# design.net
KiCad netlist of a schematic drawn in Altium Designer
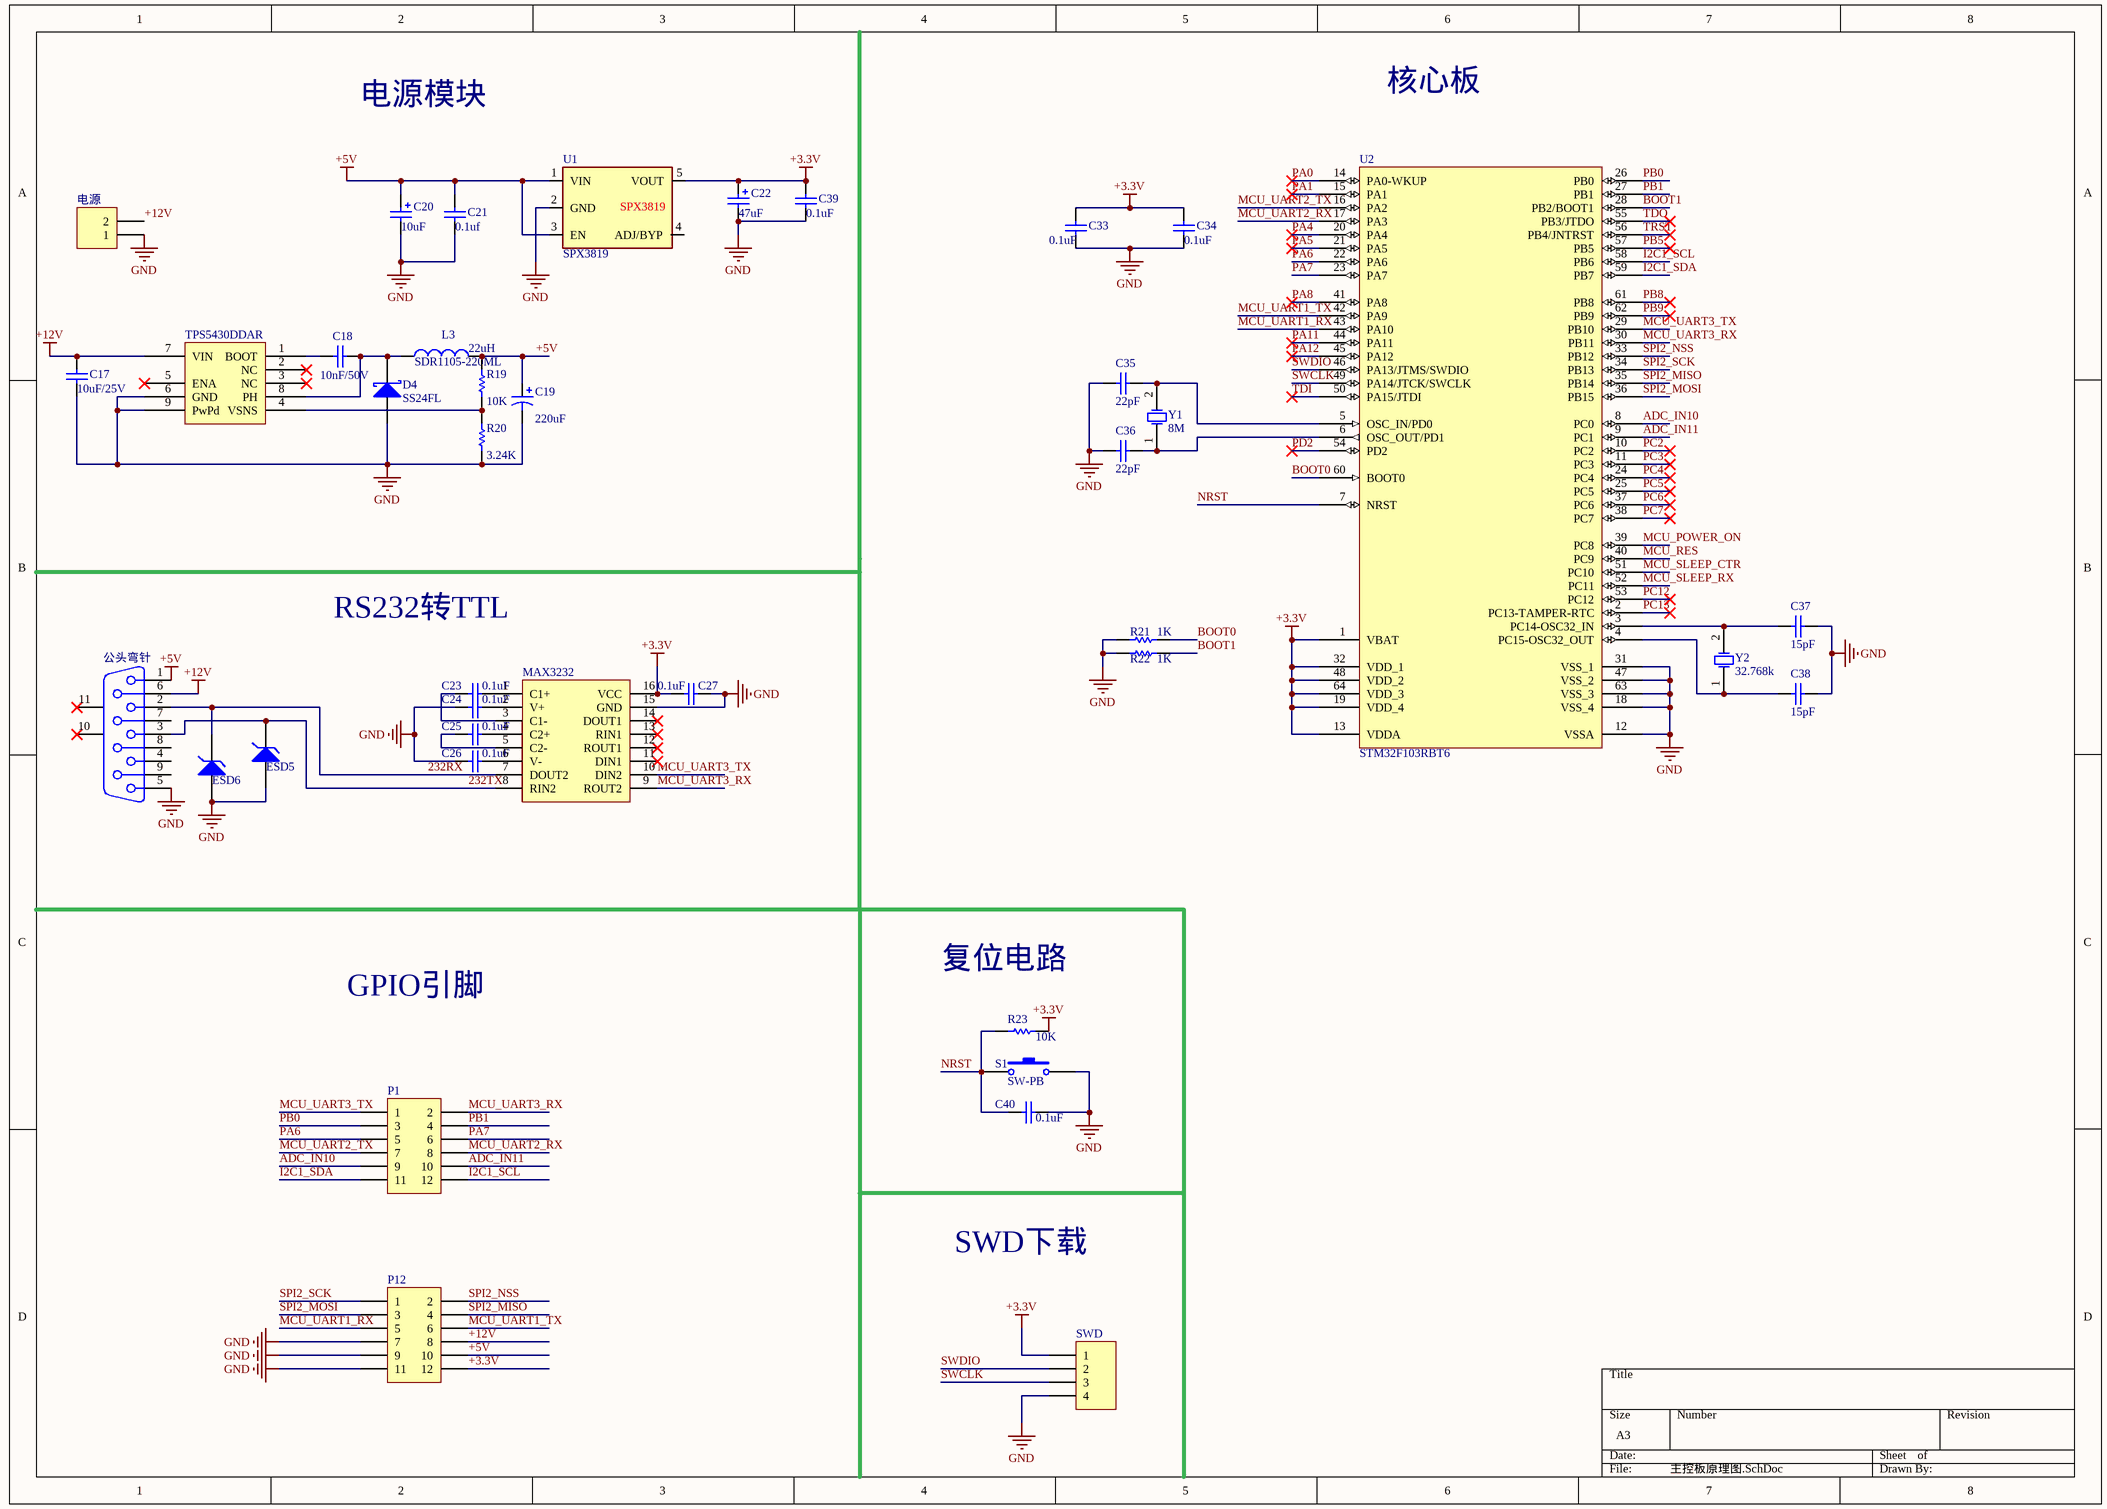
[diagram p0: 主控板原理图.SchDoc]

(export (version "E")
  (design (tool "Eeschema 10.0.6"))
  (components
    (comp (ref "C17")
      (value "10uF/25V")
      (footprint "1206")
      (description "Capacitor")
      (fields (field (name "Comment") "GRM31CR61E106KA12L") (field (name "PUBLISHER") "Altium Limited"))
      (libsource (lib "Miscellaneous Devices") (part "Cap"))
    )
    (comp (ref "C18")
      (value "10nF/50V")
      (footprint "0805")
      (description "Capacitor")
      (fields (field (name "Comment") "C0805C103K5RACTU") (field (name "PUBLISHER") "Altium Limited"))
      (libsource (lib "Miscellaneous Devices") (part "Cap"))
    )
    (comp (ref "C19")
      (value "220uF")
      (footprint "钽电容(B)")
      (description "Polarized Capacitor (Radial)")
      (fields (field (name "Comment") "6TPE220MAZB") (field (name "PUBLISHER") "Altium Limited"))
      (libsource (lib "Miscellaneous Devices") (part "Cap Pol1"))
    )
    (comp (ref "C20")
      (value "10uF")
      (footprint "1206")
      (fields (field (name "Comment") "C1206-10uF"))
      (libsource (lib "四轴旋翼") (part "C100uF"))
    )
    (comp (ref "C21")
      (value "0.1uf")
      (footprint "0805")
      (fields (field (name "Comment") "104"))
      (libsource (lib "四轴旋翼") (part "C0.1uF"))
    )
    (comp (ref "C22")
      (value "47uF")
      (footprint "1206")
      (fields (field (name "Comment") "C1206-47uF"))
      (libsource (lib "四轴旋翼") (part "C100uF"))
    )
    (comp (ref "C23")
      (value "0.1uF")
      (footprint "0805")
      (description "Capacitor")
      (fields (field (name "Comment") "104") (field (name "PUBLISHER") "Altium Limited"))
      (libsource (lib "Miscellaneous Devices") (part "Cap"))
    )
    (comp (ref "C24")
      (value "0.1uF")
      (footprint "0805")
      (description "Capacitor")
      (fields (field (name "Comment") "104") (field (name "PUBLISHER") "Altium Limited"))
      (libsource (lib "Miscellaneous Devices") (part "Cap"))
    )
    (comp (ref "C25")
      (value "0.1uF")
      (footprint "0805")
      (description "Capacitor")
      (fields (field (name "Comment") "104") (field (name "PUBLISHER") "Altium Limited"))
      (libsource (lib "Miscellaneous Devices") (part "Cap"))
    )
    (comp (ref "C26")
      (value "0.1uF")
      (footprint "0805")
      (description "Capacitor")
      (fields (field (name "Comment") "104") (field (name "PUBLISHER") "Altium Limited"))
      (libsource (lib "Miscellaneous Devices") (part "Cap"))
    )
    (comp (ref "C27")
      (value "0.1uF")
      (footprint "0805")
      (description "Capacitor")
      (fields (field (name "Comment") "104") (field (name "PUBLISHER") "Altium Limited"))
      (libsource (lib "Miscellaneous Devices") (part "Cap"))
    )
    (comp (ref "C33")
      (value "0.1uF")
      (footprint "0805")
      (description "Capacitor")
      (fields (field (name "Comment") "104") (field (name "PUBLISHER") "Altium Limited"))
      (libsource (lib "Miscellaneous Devices") (part "Cap"))
    )
    (comp (ref "C34")
      (value "0.1uF")
      (footprint "0805")
      (description "Capacitor")
      (fields (field (name "Comment") "104") (field (name "PUBLISHER") "Altium Limited"))
      (libsource (lib "Miscellaneous Devices") (part "Cap"))
    )
    (comp (ref "C35")
      (value "22pF")
      (footprint "0805")
      (description "Capacitor")
      (fields (field (name "Comment") "22") (field (name "PUBLISHER") "Altium Limited"))
      (libsource (lib "Miscellaneous Devices") (part "Cap"))
    )
    (comp (ref "C36")
      (value "22pF")
      (footprint "0805")
      (description "Capacitor")
      (fields (field (name "Comment") "22") (field (name "PUBLISHER") "Altium Limited"))
      (libsource (lib "Miscellaneous Devices") (part "Cap"))
    )
    (comp (ref "C37")
      (value "15pF")
      (footprint "0805")
      (description "Capacitor")
      (fields (field (name "Comment") "15") (field (name "PUBLISHER") "Altium Limited"))
      (libsource (lib "Miscellaneous Devices") (part "Cap"))
    )
    (comp (ref "C38")
      (value "15pF")
      (footprint "0805")
      (description "Capacitor")
      (fields (field (name "Comment") "15") (field (name "PUBLISHER") "Altium Limited"))
      (libsource (lib "Miscellaneous Devices") (part "Cap"))
    )
    (comp (ref "C39")
      (value "0.1uF")
      (footprint "0805")
      (fields (field (name "Comment") "104"))
      (libsource (lib "四轴旋翼") (part "C0.1uF"))
    )
    (comp (ref "C40")
      (value "0.1uF")
      (footprint "0805")
      (description "Capacitor")
      (fields (field (name "Comment") "104") (field (name "PUBLISHER") "Altium Limited"))
      (libsource (lib "Miscellaneous Devices") (part "Cap"))
    )
    (comp (ref "D4")
      (value "SS24FL")
      (footprint "SS24fl")
      (description "Schottky Diode")
      (fields (field (name "PUBLISHER") "Altium Limited"))
      (libsource (lib "Miscellaneous Devices") (part "D Schottky"))
    )
    (comp (ref "ESD5")
      (value "SZESD7361HT1G")
      (footprint "0603")
      (description "Zener Diode")
      (fields (field (name "PUBLISHER") "Altium Limited"))
      (libsource (lib "Miscellaneous Devices") (part "D Zener"))
    )
    (comp (ref "ESD6")
      (value "SZESD7361HT1G")
      (footprint "0603")
      (description "Zener Diode")
      (fields (field (name "PUBLISHER") "Altium Limited"))
      (libsource (lib "Miscellaneous Devices") (part "D Zener"))
    )
    (comp (ref "L3")
      (value "SDR1105-220ML")
      (footprint "inductor")
      (description "Inductor")
      (fields (field (name "ALTIUM_VALUE") "22uH") (field (name "PUBLISHER") "Altium Limited"))
      (libsource (lib "Miscellaneous Devices") (part "Inductor"))
    )
    (comp (ref "MAX3232") (value "MAX3232") (footprint "MAX3232") (libsource (lib "Schlib1") (part "MAX232")))
    (comp (ref "P1")
      (value "Header 6X2")
      (footprint "HDR6*2")
      (description "Header, 6-Pin, Dual row")
      (fields (field (name "PUBLISHER") "Altium Limited"))
      (libsource (lib "Miscellaneous Connectors") (part "Header 6X2"))
    )
    (comp (ref "P12")
      (value "Header 6X2")
      (footprint "HDR6*2")
      (description "Header, 6-Pin, Dual row")
      (fields (field (name "PUBLISHER") "Altium Limited"))
      (libsource (lib "Miscellaneous Connectors") (part "Header 6X2"))
    )
    (comp (ref "R19")
      (value "10K")
      (footprint "0805")
      (description "Resistor")
      (fields (field (name "PUBLISHER") "Altium Limited"))
      (libsource (lib "Miscellaneous Devices") (part "Res1"))
    )
    (comp (ref "R20")
      (value "3.24K")
      (footprint "0805")
      (description "Resistor")
      (fields (field (name "PUBLISHER") "Altium Limited"))
      (libsource (lib "Miscellaneous Devices") (part "Res1"))
    )
    (comp (ref "R21")
      (value "1K")
      (footprint "0805")
      (description "Resistor")
      (fields (field (name "PUBLISHER") "Altium Limited"))
      (libsource (lib "Miscellaneous Devices") (part "Res1"))
    )
    (comp (ref "R22")
      (value "1K")
      (footprint "0805")
      (description "Resistor")
      (fields (field (name "PUBLISHER") "Altium Limited"))
      (libsource (lib "Miscellaneous Devices") (part "Res1"))
    )
    (comp (ref "R23")
      (value "10K")
      (footprint "0805")
      (description "Resistor")
      (fields (field (name "PUBLISHER") "Altium Limited"))
      (libsource (lib "Miscellaneous Devices") (part "Res1"))
    )
    (comp (ref "S1")
      (value "SW-PB")
      (footprint "key")
      (description "Switch")
      (fields (field (name "PUBLISHER") "Altium Limited"))
      (libsource (lib "Miscellaneous Devices") (part "SW-PB"))
    )
    (comp (ref "SWD")
      (value "Header 4")
      (footprint "SWD")
      (description "Header, 4-Pin")
      (fields (field (name "PUBLISHER") "Altium Limited"))
      (libsource (lib "Miscellaneous Connectors") (part "Header 4"))
    )
    (comp (ref "TPS5430DDAR")
      (value "TPS5430DDAR")
      (footprint "TPS5430")
      (libsource (lib "Schlib1") (part "TPS5430"))
    )
    (comp (ref "U1")
      (value "SPX3819")
      (footprint "SOT-23-5")
      (libsource (lib "MX485_GSM_WIFI") (part "SPX3819"))
    )
    (comp (ref "U2")
      (value "STM32F103RBT6")
      (footprint "STM32f103RBT6")
      (description "STM32 ARM-based 32-bit MCU with 128 Kbytes Flash, 64-pin LQFP, Industrial Temperature")
      (fields (field (name "PUBLISHER") "Altium Limited"))
      (libsource (lib "ST Microcontroller 32-Bit STM32") (part "STM32F103RBT6"))
    )
    (comp (ref "Y1")
      (value "8M")
      (footprint "XTAL-B")
      (description "Crystal Oscillator")
      (fields (field (name "PUBLISHER") "Altium Limited"))
      (libsource (lib "Miscellaneous Devices") (part "XTAL"))
    )
    (comp (ref "Y2")
      (value "32.768k")
      (footprint "XTAL-B")
      (description "Crystal Oscillator")
      (fields (field (name "PUBLISHER") "Altium Limited"))
      (libsource (lib "Miscellaneous Devices") (part "XTAL"))
    )
    (comp (ref "公头弯针")
      (value "RS232公头弯针")
      (footprint "RS232")
      (description "Receptacle Assembly, 9 Position, Right Angle")
      (fields (field (name "PUBLISHER") "Altium Limited"))
      (libsource (lib "Miscellaneous Connectors") (part "D Connector 9"))
    )
    (comp (ref "电源")
      (value "DUANZI")
      (footprint "DUANZI")
      (description "Header, 2-Pin")
      (fields (field (name "PUBLISHER") "Altium Limited"))
      (libsource (lib "Miscellaneous Connectors") (part "Header 2"))
    )
  )
  (nets
    (net (code "1") (name "+3.3V") (class "Default")
      (node (ref "C22") (pin "1") (pinfunction "1_1") (pintype "passive"))
      (node (ref "C27") (pin "2") (pinfunction "2_2") (pintype "passive"))
      (node (ref "C33") (pin "1") (pinfunction "1_1") (pintype "passive"))
      (node (ref "C34") (pin "1") (pinfunction "1_1") (pintype "passive"))
      (node (ref "C39") (pin "2") (pinfunction "2_2") (pintype "passive"))
      (node (ref "MAX3232") (pin "16") (pinfunction "VCC_16") (pintype "passive"))
      (node (ref "P12") (pin "12") (pinfunction "12_12") (pintype "passive"))
      (node (ref "R23") (pin "2") (pinfunction "2_2") (pintype "passive"))
      (node (ref "SWD") (pin "1") (pinfunction "1_1") (pintype "passive"))
      (node (ref "U1") (pin "5") (pinfunction "VOUT_5") (pintype "passive"))
      (node (ref "U2") (pin "1") (pinfunction "VBAT_1") (pintype "power_in"))
      (node (ref "U2") (pin "13") (pinfunction "VDDA_13") (pintype "power_in"))
      (node (ref "U2") (pin "19") (pinfunction "VDD_4_19") (pintype "power_in"))
      (node (ref "U2") (pin "32") (pinfunction "VDD_1_32") (pintype "power_in"))
      (node (ref "U2") (pin "48") (pinfunction "VDD_2_48") (pintype "power_in"))
      (node (ref "U2") (pin "64") (pinfunction "VDD_3_64") (pintype "power_in"))
    )
    (net (code "2") (name "+5V") (class "Default")
      (node (ref "C19") (pin "1") (pinfunction "1_1") (pintype "passive"))
      (node (ref "C20") (pin "1") (pinfunction "1_1") (pintype "passive"))
      (node (ref "C21") (pin "2") (pinfunction "2_2") (pintype "passive"))
      (node (ref "L3") (pin "2") (pinfunction "2_2") (pintype "passive"))
      (node (ref "P12") (pin "10") (pinfunction "10_10") (pintype "passive"))
      (node (ref "R19") (pin "2") (pinfunction "2_2") (pintype "passive"))
      (node (ref "U1") (pin "1") (pinfunction "VIN_1") (pintype "passive"))
      (node (ref "U1") (pin "3") (pinfunction "EN_3") (pintype "passive"))
      (node (ref "公头弯针") (pin "1") (pinfunction "1_1") (pintype "passive"))
    )
    (net (code "3") (name "+12V") (class "Default")
      (node (ref "C17") (pin "1") (pinfunction "1_1") (pintype "passive"))
      (node (ref "P12") (pin "8") (pinfunction "8_8") (pintype "passive"))
      (node (ref "TPS5430DDAR") (pin "7") (pinfunction "VIN_7") (pintype "passive"))
      (node (ref "公头弯针") (pin "6") (pinfunction "6_6") (pintype "passive"))
      (node (ref "电源") (pin "2") (pinfunction "2_2") (pintype "passive"))
    )
    (net (code "4") (name "/232RX") (class "Default")
      (node (ref "ESD6") (pin "2") (pinfunction "K_2") (pintype "passive"))
      (node (ref "MAX3232") (pin "7") (pinfunction "DOUT2_7") (pintype "passive"))
      (node (ref "公头弯针") (pin "2") (pinfunction "2_2") (pintype "passive"))
    )
    (net (code "5") (name "/232TX") (class "Default")
      (node (ref "ESD5") (pin "2") (pinfunction "K_2") (pintype "passive"))
      (node (ref "MAX3232") (pin "8") (pinfunction "RIN2_8") (pintype "passive"))
      (node (ref "公头弯针") (pin "3") (pinfunction "3_3") (pintype "passive"))
    )
    (net (code "6") (name "/ADC_IN10") (class "Default")
      (node (ref "P1") (pin "9") (pinfunction "9_9") (pintype "passive"))
      (node (ref "U2") (pin "8") (pinfunction "PC0_8") (pintype "bidirectional"))
    )
    (net (code "7") (name "/ADC_IN11") (class "Default")
      (node (ref "P1") (pin "10") (pinfunction "10_10") (pintype "passive"))
      (node (ref "U2") (pin "9") (pinfunction "PC1_9") (pintype "bidirectional"))
    )
    (net (code "8") (name "/BOOT0") (class "Default")
      (node (ref "R21") (pin "1") (pinfunction "1_1") (pintype "passive"))
      (node (ref "U2") (pin "60") (pinfunction "BOOT0_60") (pintype "input"))
    )
    (net (code "9") (name "/BOOT1") (class "Default")
      (node (ref "R22") (pin "1") (pinfunction "1_1") (pintype "passive"))
      (node (ref "U2") (pin "28") (pinfunction "PB2/BOOT1_28") (pintype "bidirectional"))
    )
    (net (code "10") (name "/I2C1_SCL") (class "Default")
      (node (ref "P1") (pin "12") (pinfunction "12_12") (pintype "passive"))
      (node (ref "U2") (pin "58") (pinfunction "PB6_58") (pintype "bidirectional"))
    )
    (net (code "11") (name "/I2C1_SDA") (class "Default")
      (node (ref "P1") (pin "11") (pinfunction "11_11") (pintype "passive"))
      (node (ref "U2") (pin "59") (pinfunction "PB7_59") (pintype "bidirectional"))
    )
    (net (code "12") (name "/MCU_POWER_ON") (class "Default")
      (node (ref "U2") (pin "39") (pinfunction "PC8_39") (pintype "bidirectional"))
    )
    (net (code "13") (name "/MCU_RES") (class "Default")
      (node (ref "U2") (pin "40") (pinfunction "PC9_40") (pintype "bidirectional"))
    )
    (net (code "14") (name "/MCU_SLEEP_CTR") (class "Default")
      (node (ref "U2") (pin "51") (pinfunction "PC10_51") (pintype "bidirectional"))
    )
    (net (code "15") (name "/MCU_SLEEP_RX") (class "Default")
      (node (ref "U2") (pin "52") (pinfunction "PC11_52") (pintype "bidirectional"))
    )
    (net (code "16") (name "/MCU_UART1_RX") (class "Default")
      (node (ref "P12") (pin "5") (pinfunction "5_5") (pintype "passive"))
      (node (ref "U2") (pin "43") (pinfunction "PA10_43") (pintype "bidirectional"))
    )
    (net (code "17") (name "/MCU_UART1_TX") (class "Default")
      (node (ref "P12") (pin "6") (pinfunction "6_6") (pintype "passive"))
      (node (ref "U2") (pin "42") (pinfunction "PA9_42") (pintype "bidirectional"))
    )
    (net (code "18") (name "/MCU_UART2_RX") (class "Default")
      (node (ref "P1") (pin "8") (pinfunction "8_8") (pintype "passive"))
      (node (ref "U2") (pin "17") (pinfunction "PA3_17") (pintype "bidirectional"))
    )
    (net (code "19") (name "/MCU_UART2_TX") (class "Default")
      (node (ref "P1") (pin "7") (pinfunction "7_7") (pintype "passive"))
      (node (ref "U2") (pin "16") (pinfunction "PA2_16") (pintype "bidirectional"))
    )
    (net (code "20") (name "/MCU_UART3_RX") (class "Default")
      (node (ref "MAX3232") (pin "9") (pinfunction "ROUT2_9") (pintype "passive"))
      (node (ref "P1") (pin "2") (pinfunction "2_2") (pintype "passive"))
      (node (ref "U2") (pin "30") (pinfunction "PB11_30") (pintype "bidirectional"))
    )
    (net (code "21") (name "/MCU_UART3_TX") (class "Default")
      (node (ref "MAX3232") (pin "10") (pinfunction "DIN2_10") (pintype "passive"))
      (node (ref "P1") (pin "1") (pinfunction "1_1") (pintype "passive"))
      (node (ref "U2") (pin "29") (pinfunction "PB10_29") (pintype "bidirectional"))
    )
    (net (code "22") (name "/NRST") (class "Default")
      (node (ref "C40") (pin "1") (pinfunction "1_1") (pintype "passive"))
      (node (ref "R23") (pin "1") (pinfunction "1_1") (pintype "passive"))
      (node (ref "S1") (pin "1") (pinfunction "1_1") (pintype "passive"))
      (node (ref "U2") (pin "7") (pinfunction "NRST_7") (pintype "bidirectional"))
    )
    (net (code "23") (name "/PA0") (class "Default")
      (node (ref "U2") (pin "14") (pinfunction "PA0-WKUP_14") (pintype "bidirectional+no_connect"))
    )
    (net (code "24") (name "/PA1") (class "Default")
      (node (ref "U2") (pin "15") (pinfunction "PA1_15") (pintype "bidirectional+no_connect"))
    )
    (net (code "25") (name "/PA4") (class "Default")
      (node (ref "U2") (pin "20") (pinfunction "PA4_20") (pintype "bidirectional+no_connect"))
    )
    (net (code "26") (name "/PA5") (class "Default")
      (node (ref "U2") (pin "21") (pinfunction "PA5_21") (pintype "bidirectional+no_connect"))
    )
    (net (code "27") (name "/PA6") (class "Default")
      (node (ref "P1") (pin "5") (pinfunction "5_5") (pintype "passive"))
      (node (ref "U2") (pin "22") (pinfunction "PA6_22") (pintype "bidirectional"))
    )
    (net (code "28") (name "/PA7") (class "Default")
      (node (ref "P1") (pin "6") (pinfunction "6_6") (pintype "passive"))
      (node (ref "U2") (pin "23") (pinfunction "PA7_23") (pintype "bidirectional"))
    )
    (net (code "29") (name "/PA8") (class "Default")
      (node (ref "U2") (pin "41") (pinfunction "PA8_41") (pintype "bidirectional+no_connect"))
    )
    (net (code "30") (name "/PA11") (class "Default")
      (node (ref "U2") (pin "44") (pinfunction "PA11_44") (pintype "bidirectional+no_connect"))
    )
    (net (code "31") (name "/PA12") (class "Default")
      (node (ref "U2") (pin "45") (pinfunction "PA12_45") (pintype "bidirectional+no_connect"))
    )
    (net (code "32") (name "/PB0") (class "Default")
      (node (ref "P1") (pin "3") (pinfunction "3_3") (pintype "passive"))
      (node (ref "U2") (pin "26") (pinfunction "PB0_26") (pintype "bidirectional"))
    )
    (net (code "33") (name "/PB1") (class "Default")
      (node (ref "P1") (pin "4") (pinfunction "4_4") (pintype "passive"))
      (node (ref "U2") (pin "27") (pinfunction "PB1_27") (pintype "bidirectional"))
    )
    (net (code "34") (name "/PB5") (class "Default")
      (node (ref "U2") (pin "57") (pinfunction "PB5_57") (pintype "bidirectional+no_connect"))
    )
    (net (code "35") (name "/PB8") (class "Default")
      (node (ref "U2") (pin "61") (pinfunction "PB8_61") (pintype "bidirectional+no_connect"))
    )
    (net (code "36") (name "/PB9") (class "Default")
      (node (ref "U2") (pin "62") (pinfunction "PB9_62") (pintype "bidirectional+no_connect"))
    )
    (net (code "37") (name "/PC2") (class "Default")
      (node (ref "U2") (pin "10") (pinfunction "PC2_10") (pintype "bidirectional+no_connect"))
    )
    (net (code "38") (name "/PC3") (class "Default")
      (node (ref "U2") (pin "11") (pinfunction "PC3_11") (pintype "bidirectional+no_connect"))
    )
    (net (code "39") (name "/PC4") (class "Default")
      (node (ref "U2") (pin "24") (pinfunction "PC4_24") (pintype "bidirectional+no_connect"))
    )
    (net (code "40") (name "/PC5") (class "Default")
      (node (ref "U2") (pin "25") (pinfunction "PC5_25") (pintype "bidirectional+no_connect"))
    )
    (net (code "41") (name "/PC6") (class "Default")
      (node (ref "U2") (pin "37") (pinfunction "PC6_37") (pintype "bidirectional+no_connect"))
    )
    (net (code "42") (name "/PC7") (class "Default")
      (node (ref "U2") (pin "38") (pinfunction "PC7_38") (pintype "bidirectional+no_connect"))
    )
    (net (code "43") (name "/PC12") (class "Default")
      (node (ref "U2") (pin "53") (pinfunction "PC12_53") (pintype "bidirectional+no_connect"))
    )
    (net (code "44") (name "/PC13") (class "Default")
      (node (ref "U2") (pin "2") (pinfunction "PC13-TAMPER-RTC_2") (pintype "bidirectional+no_connect"))
    )
    (net (code "45") (name "/PD2") (class "Default")
      (node (ref "U2") (pin "54") (pinfunction "PD2_54") (pintype "bidirectional+no_connect"))
    )
    (net (code "46") (name "/SPI2_MISO") (class "Default")
      (node (ref "P12") (pin "4") (pinfunction "4_4") (pintype "passive"))
      (node (ref "U2") (pin "35") (pinfunction "PB14_35") (pintype "bidirectional"))
    )
    (net (code "47") (name "/SPI2_MOSI") (class "Default")
      (node (ref "P12") (pin "3") (pinfunction "3_3") (pintype "passive"))
      (node (ref "U2") (pin "36") (pinfunction "PB15_36") (pintype "bidirectional"))
    )
    (net (code "48") (name "/SPI2_NSS") (class "Default")
      (node (ref "P12") (pin "2") (pinfunction "2_2") (pintype "passive"))
      (node (ref "U2") (pin "33") (pinfunction "PB12_33") (pintype "bidirectional"))
    )
    (net (code "49") (name "/SPI2_SCK") (class "Default")
      (node (ref "P12") (pin "1") (pinfunction "1_1") (pintype "passive"))
      (node (ref "U2") (pin "34") (pinfunction "PB13_34") (pintype "bidirectional"))
    )
    (net (code "50") (name "/SWCLK") (class "Default")
      (node (ref "SWD") (pin "3") (pinfunction "3_3") (pintype "passive"))
      (node (ref "U2") (pin "49") (pinfunction "PA14/JTCK/SWCLK_49") (pintype "bidirectional"))
    )
    (net (code "51") (name "/SWDIO") (class "Default")
      (node (ref "SWD") (pin "2") (pinfunction "2_2") (pintype "passive"))
      (node (ref "U2") (pin "46") (pinfunction "PA13/JTMS/SWDIO_46") (pintype "bidirectional"))
    )
    (net (code "52") (name "/TDI") (class "Default")
      (node (ref "U2") (pin "50") (pinfunction "PA15/JTDI_50") (pintype "bidirectional+no_connect"))
    )
    (net (code "53") (name "/TDO") (class "Default")
      (node (ref "U2") (pin "55") (pinfunction "PB3/JTDO_55") (pintype "bidirectional+no_connect"))
    )
    (net (code "54") (name "/TRST") (class "Default")
      (node (ref "U2") (pin "56") (pinfunction "PB4/JNTRST_56") (pintype "bidirectional+no_connect"))
    )
    (net (code "55") (name "GND") (class "Default")
      (node (ref "C17") (pin "2") (pinfunction "2_2") (pintype "passive"))
      (node (ref "C19") (pin "2") (pinfunction "2_2") (pintype "passive"))
      (node (ref "C20") (pin "2") (pinfunction "2_2") (pintype "passive"))
      (node (ref "C21") (pin "1") (pinfunction "1_1") (pintype "passive"))
      (node (ref "C22") (pin "2") (pinfunction "2_2") (pintype "passive"))
      (node (ref "C24") (pin "1") (pinfunction "1_1") (pintype "passive"))
      (node (ref "C26") (pin "1") (pinfunction "1_1") (pintype "passive"))
      (node (ref "C27") (pin "1") (pinfunction "1_1") (pintype "passive"))
      (node (ref "C33") (pin "2") (pinfunction "2_2") (pintype "passive"))
      (node (ref "C34") (pin "2") (pinfunction "2_2") (pintype "passive"))
      (node (ref "C35") (pin "1") (pinfunction "1_1") (pintype "passive"))
      (node (ref "C36") (pin "1") (pinfunction "1_1") (pintype "passive"))
      (node (ref "C37") (pin "2") (pinfunction "2_2") (pintype "passive"))
      (node (ref "C38") (pin "2") (pinfunction "2_2") (pintype "passive"))
      (node (ref "C39") (pin "1") (pinfunction "1_1") (pintype "passive"))
      (node (ref "C40") (pin "2") (pinfunction "2_2") (pintype "passive"))
      (node (ref "D4") (pin "1") (pinfunction "A_1") (pintype "passive"))
      (node (ref "ESD5") (pin "1") (pinfunction "A_1") (pintype "passive"))
      (node (ref "ESD6") (pin "1") (pinfunction "A_1") (pintype "passive"))
      (node (ref "MAX3232") (pin "15") (pinfunction "GND_15") (pintype "passive"))
      (node (ref "P12") (pin "11") (pinfunction "11_11") (pintype "passive"))
      (node (ref "P12") (pin "7") (pinfunction "7_7") (pintype "passive"))
      (node (ref "P12") (pin "9") (pinfunction "9_9") (pintype "passive"))
      (node (ref "R20") (pin "1") (pinfunction "1_1") (pintype "passive"))
      (node (ref "R21") (pin "2") (pinfunction "2_2") (pintype "passive"))
      (node (ref "R22") (pin "2") (pinfunction "2_2") (pintype "passive"))
      (node (ref "S1") (pin "2") (pinfunction "2_2") (pintype "passive"))
      (node (ref "SWD") (pin "4") (pinfunction "4_4") (pintype "passive"))
      (node (ref "TPS5430DDAR") (pin "6") (pinfunction "GND_6") (pintype "passive"))
      (node (ref "TPS5430DDAR") (pin "9") (pinfunction "PwPd_9") (pintype "passive"))
      (node (ref "U1") (pin "2") (pinfunction "GND_2") (pintype "passive"))
      (node (ref "U2") (pin "12") (pinfunction "VSSA_12") (pintype "power_in"))
      (node (ref "U2") (pin "18") (pinfunction "VSS_4_18") (pintype "power_in"))
      (node (ref "U2") (pin "31") (pinfunction "VSS_1_31") (pintype "power_in"))
      (node (ref "U2") (pin "47") (pinfunction "VSS_2_47") (pintype "power_in"))
      (node (ref "U2") (pin "63") (pinfunction "VSS_3_63") (pintype "power_in"))
      (node (ref "公头弯针") (pin "5") (pinfunction "5_5") (pintype "passive"))
      (node (ref "电源") (pin "1") (pinfunction "1_1") (pintype "passive"))
    )
    (net (code "56") (name "Net-(D4-K)") (class "Default")
      (node (ref "C18") (pin "2") (pinfunction "2_2") (pintype "passive"))
      (node (ref "D4") (pin "2") (pinfunction "K_2") (pintype "passive"))
      (node (ref "L3") (pin "1") (pinfunction "1_1") (pintype "passive"))
      (node (ref "TPS5430DDAR") (pin "8") (pinfunction "PH_8") (pintype "passive"))
    )
    (net (code "57") (name "Net-(MAX3232-C1+)") (class "Default")
      (node (ref "C23") (pin "2") (pinfunction "2_2") (pintype "passive"))
      (node (ref "MAX3232") (pin "1") (pinfunction "C1+_1") (pintype "passive"))
    )
    (net (code "58") (name "Net-(MAX3232-C1-)") (class "Default")
      (node (ref "C23") (pin "1") (pinfunction "1_1") (pintype "passive"))
      (node (ref "MAX3232") (pin "3") (pinfunction "C1-_3") (pintype "passive"))
    )
    (net (code "59") (name "Net-(MAX3232-C2+)") (class "Default")
      (node (ref "C25") (pin "2") (pinfunction "2_2") (pintype "passive"))
      (node (ref "MAX3232") (pin "4") (pinfunction "C2+_4") (pintype "passive"))
    )
    (net (code "60") (name "Net-(MAX3232-C2-)") (class "Default")
      (node (ref "C25") (pin "1") (pinfunction "1_1") (pintype "passive"))
      (node (ref "MAX3232") (pin "5") (pinfunction "C2-_5") (pintype "passive"))
    )
    (net (code "61") (name "Net-(MAX3232-V+)") (class "Default")
      (node (ref "C24") (pin "2") (pinfunction "2_2") (pintype "passive"))
      (node (ref "MAX3232") (pin "2") (pinfunction "V+_2") (pintype "passive"))
    )
    (net (code "62") (name "Net-(MAX3232-V-)") (class "Default")
      (node (ref "C26") (pin "2") (pinfunction "2_2") (pintype "passive"))
      (node (ref "MAX3232") (pin "6") (pinfunction "V-_6") (pintype "passive"))
    )
    (net (code "63") (name "Net-(TPS5430DDAR-BOOT)") (class "Default")
      (node (ref "C18") (pin "1") (pinfunction "1_1") (pintype "passive"))
      (node (ref "TPS5430DDAR") (pin "1") (pinfunction "BOOT_1") (pintype "passive"))
    )
    (net (code "64") (name "Net-(TPS5430DDAR-VSNS)") (class "Default")
      (node (ref "R19") (pin "1") (pinfunction "1_1") (pintype "passive"))
      (node (ref "R20") (pin "2") (pinfunction "2_2") (pintype "passive"))
      (node (ref "TPS5430DDAR") (pin "4") (pinfunction "VSNS_4") (pintype "passive"))
    )
    (net (code "65") (name "Net-(U2-OSC_IN{slash}PD0)") (class "Default")
      (node (ref "C35") (pin "2") (pinfunction "2_2") (pintype "passive"))
      (node (ref "U2") (pin "5") (pinfunction "OSC_IN/PD0_5") (pintype "input"))
      (node (ref "Y1") (pin "2") (pinfunction "OSC2_2") (pintype "passive"))
    )
    (net (code "66") (name "Net-(U2-OSC_OUT{slash}PD1)") (class "Default")
      (node (ref "C36") (pin "2") (pinfunction "2_2") (pintype "passive"))
      (node (ref "U2") (pin "6") (pinfunction "OSC_OUT/PD1_6") (pintype "output"))
      (node (ref "Y1") (pin "1") (pinfunction "OSC1_1") (pintype "passive"))
    )
    (net (code "67") (name "Net-(U2-PC14-OSC32_IN)") (class "Default")
      (node (ref "C37") (pin "1") (pinfunction "1_1") (pintype "passive"))
      (node (ref "U2") (pin "3") (pinfunction "PC14-OSC32_IN_3") (pintype "bidirectional"))
      (node (ref "Y2") (pin "2") (pinfunction "OSC2_2") (pintype "passive"))
    )
    (net (code "68") (name "Net-(U2-PC15-OSC32_OUT)") (class "Default")
      (node (ref "C38") (pin "1") (pinfunction "1_1") (pintype "passive"))
      (node (ref "U2") (pin "4") (pinfunction "PC15-OSC32_OUT_4") (pintype "bidirectional"))
      (node (ref "Y2") (pin "1") (pinfunction "OSC1_1") (pintype "passive"))
    )
    (net (code "69") (name "unconnected-(MAX3232-DIN1-Pad11)") (class "Default")
      (node (ref "MAX3232") (pin "11") (pinfunction "DIN1_11") (pintype "passive+no_connect"))
    )
    (net (code "70") (name "unconnected-(MAX3232-DOUT1-Pad14)") (class "Default")
      (node (ref "MAX3232") (pin "14") (pinfunction "DOUT1_14") (pintype "passive+no_connect"))
    )
    (net (code "71") (name "unconnected-(MAX3232-RIN1-Pad13)") (class "Default")
      (node (ref "MAX3232") (pin "13") (pinfunction "RIN1_13") (pintype "passive+no_connect"))
    )
    (net (code "72") (name "unconnected-(MAX3232-ROUT1-Pad12)") (class "Default")
      (node (ref "MAX3232") (pin "12") (pinfunction "ROUT1_12") (pintype "passive+no_connect"))
    )
    (net (code "73") (name "unconnected-(TPS5430DDAR-ENA-Pad5)") (class "Default")
      (node (ref "TPS5430DDAR") (pin "5") (pinfunction "ENA_5") (pintype "passive+no_connect"))
    )
    (net (code "74") (name "unconnected-(TPS5430DDAR-NC-Pad2)") (class "Default")
      (node (ref "TPS5430DDAR") (pin "2") (pinfunction "NC_2") (pintype "passive+no_connect"))
    )
    (net (code "75") (name "unconnected-(TPS5430DDAR-NC-Pad3)") (class "Default")
      (node (ref "TPS5430DDAR") (pin "3") (pinfunction "NC_3") (pintype "passive+no_connect"))
    )
    (net (code "76") (name "unconnected-(U1-ADJ{slash}BYP-Pad4)") (class "Default")
      (node (ref "U1") (pin "4") (pinfunction "ADJ/BYP_4") (pintype "passive"))
    )
    (net (code "77") (name "unconnected-(公头弯针-MH1-Pad10)") (class "Default")
      (node (ref "公头弯针") (pin "10") (pinfunction "MH1_10") (pintype "passive+no_connect"))
    )
    (net (code "78") (name "unconnected-(公头弯针-MH2-Pad11)") (class "Default")
      (node (ref "公头弯针") (pin "11") (pinfunction "MH2_11") (pintype "passive+no_connect"))
    )
    (net (code "79") (name "unconnected-(公头弯针-Pad4)") (class "Default")
      (node (ref "公头弯针") (pin "4") (pinfunction "4_4") (pintype "passive"))
    )
    (net (code "80") (name "unconnected-(公头弯针-Pad7)") (class "Default")
      (node (ref "公头弯针") (pin "7") (pinfunction "7_7") (pintype "passive"))
    )
    (net (code "81") (name "unconnected-(公头弯针-Pad8)") (class "Default")
      (node (ref "公头弯针") (pin "8") (pinfunction "8_8") (pintype "passive"))
    )
    (net (code "82") (name "unconnected-(公头弯针-Pad9)") (class "Default")
      (node (ref "公头弯针") (pin "9") (pinfunction "9_9") (pintype "passive"))
    )
  )
)
